# 5V-Regulator.net
KiCad netlist of a schematic drawn in Altium Designer
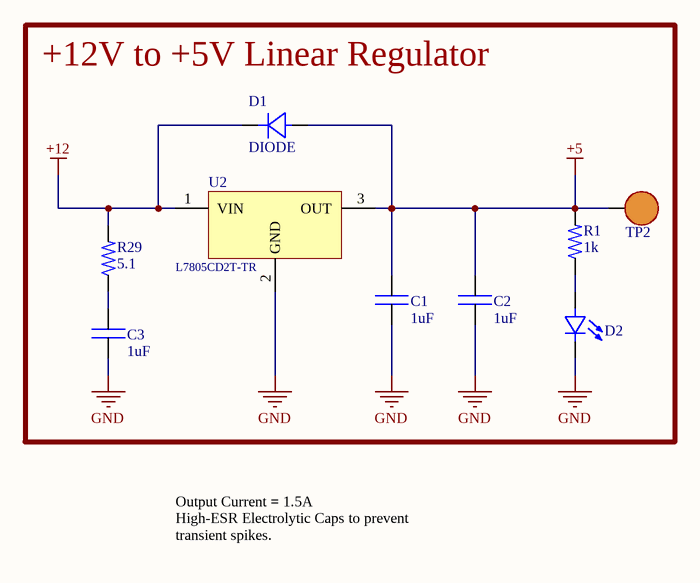
[diagram p0: 5V-Regulator.SchDoc]

(export (version "E")
  (design (tool "Eeschema 10.0.6"))
  (components
    (comp (ref "C1")
      (value "1uF")
      (footprint "Beethoven-clock:0402C")
      (description "Capacitor")
      (fields (field (name "MFR") "Murata Electronics") (field (name "Comment") "CAP"))
      (libsource (lib "Beethoven-clock") (part "CAP"))
    )
    (comp (ref "C2")
      (value "1uF")
      (footprint "Beethoven-clock:0402C")
      (description "Capacitor")
      (fields (field (name "MFR") "Murata Electronics") (field (name "Comment") "CAP"))
      (libsource (lib "Beethoven-clock") (part "CAP"))
    )
    (comp (ref "C3")
      (value "1uF")
      (footprint "Beethoven-clock:0402C")
      (description "Capacitor")
      (fields (field (name "MFR") "Murata Electronics") (field (name "Comment") "CAP"))
      (libsource (lib "Beethoven-clock") (part "CAP"))
    )
    (comp (ref "D1")
      (value "DIODE")
      (footprint "Beethoven-clock:DO-214AC")
      (description "DIODE GEN PURP")
      (fields (field (name "MFR") "Micro Commercial Co"))
      (libsource (lib "Beethoven-clock") (part "DIODE"))
    )
    (comp (ref "D2")
      (value "LED - single")
      (footprint "Beethoven-clock:LED - 0603")
      (description "LED")
      (fields (field (name "MFR") "DNS"))
      (libsource (lib "Beethoven-clock") (part "LED - single"))
    )
    (comp (ref "R1")
      (value "1k")
      (footprint "Beethoven-clock:0402R")
      (description "Resistor")
      (fields (field (name "MFR") "YAGEO") (field (name "Comment") "RES"))
      (libsource (lib "Beethoven-clock") (part "RES"))
    )
    (comp (ref "R29")
      (value "5.1")
      (footprint "Beethoven-clock:0805R")
      (description "Resistor")
      (fields (field (name "MFR") "Rohm Semiconductor") (field (name "Comment") "RES"))
      (libsource (lib "Beethoven-clock") (part "RES"))
    )
    (comp (ref "TP2")
      (value "RCWCTE")
      (footprint "Beethoven-clock:RCWCTE")
      (description "Test Point, Surface Mount")
      (fields (field (name "MFR") "KOA Speer Electronics, Inc."))
      (libsource (lib "Beethoven-clock") (part "TEST POINT"))
    )
    (comp (ref "U2")
      (value "L7805CD2T-TR")
      (footprint "Beethoven-clock:D2PAK")
      (description "Linear Voltage Regulator IC Positive Fixed 1 Output 1.5A D2PAK")
      (fields (field (name "MFR") "STMicroelectronics"))
      (libsource (lib "Beethoven-clock") (part "LIN REG 5V 1.5A 35V"))
    )
  )
  (nets
    (net (code "1") (name "+5") (class "Default")
      (node (ref "C1") (pin "2") (pinfunction "2_2") (pintype "passive"))
      (node (ref "C2") (pin "2") (pinfunction "2_2") (pintype "passive"))
      (node (ref "D1") (pin "A") (pinfunction "A_A") (pintype "passive"))
      (node (ref "R1") (pin "2") (pinfunction "2_2") (pintype "passive"))
      (node (ref "TP2") (pin "1") (pinfunction "0_1") (pintype "passive"))
      (node (ref "U2") (pin "3") (pinfunction "OUT_3") (pintype "passive"))
    )
    (net (code "2") (name "+12") (class "Default")
      (node (ref "D1") (pin "K") (pinfunction "K_K") (pintype "passive"))
      (node (ref "R29") (pin "2") (pinfunction "2_2") (pintype "passive"))
      (node (ref "U2") (pin "1") (pinfunction "VIN_1") (pintype "passive"))
    )
    (net (code "3") (name "GND") (class "Default")
      (node (ref "C1") (pin "1") (pinfunction "1_1") (pintype "passive"))
      (node (ref "C2") (pin "1") (pinfunction "1_1") (pintype "passive"))
      (node (ref "C3") (pin "1") (pinfunction "1_1") (pintype "passive"))
      (node (ref "D2") (pin "2") (pinfunction "C_2") (pintype "passive"))
      (node (ref "U2") (pin "2") (pinfunction "GND_2") (pintype "passive"))
    )
    (net (code "4") (name "Net-(C3-Pad2)") (class "Default")
      (node (ref "C3") (pin "2") (pinfunction "2_2") (pintype "passive"))
      (node (ref "R29") (pin "1") (pinfunction "1_1") (pintype "passive"))
    )
    (net (code "5") (name "Net-(D2-A)") (class "Default")
      (node (ref "D2") (pin "1") (pinfunction "A_1") (pintype "passive"))
      (node (ref "R1") (pin "1") (pinfunction "1_1") (pintype "passive"))
    )
  )
)
